# LoRa-Power.net
KiCad netlist of a schematic drawn in EAGLE
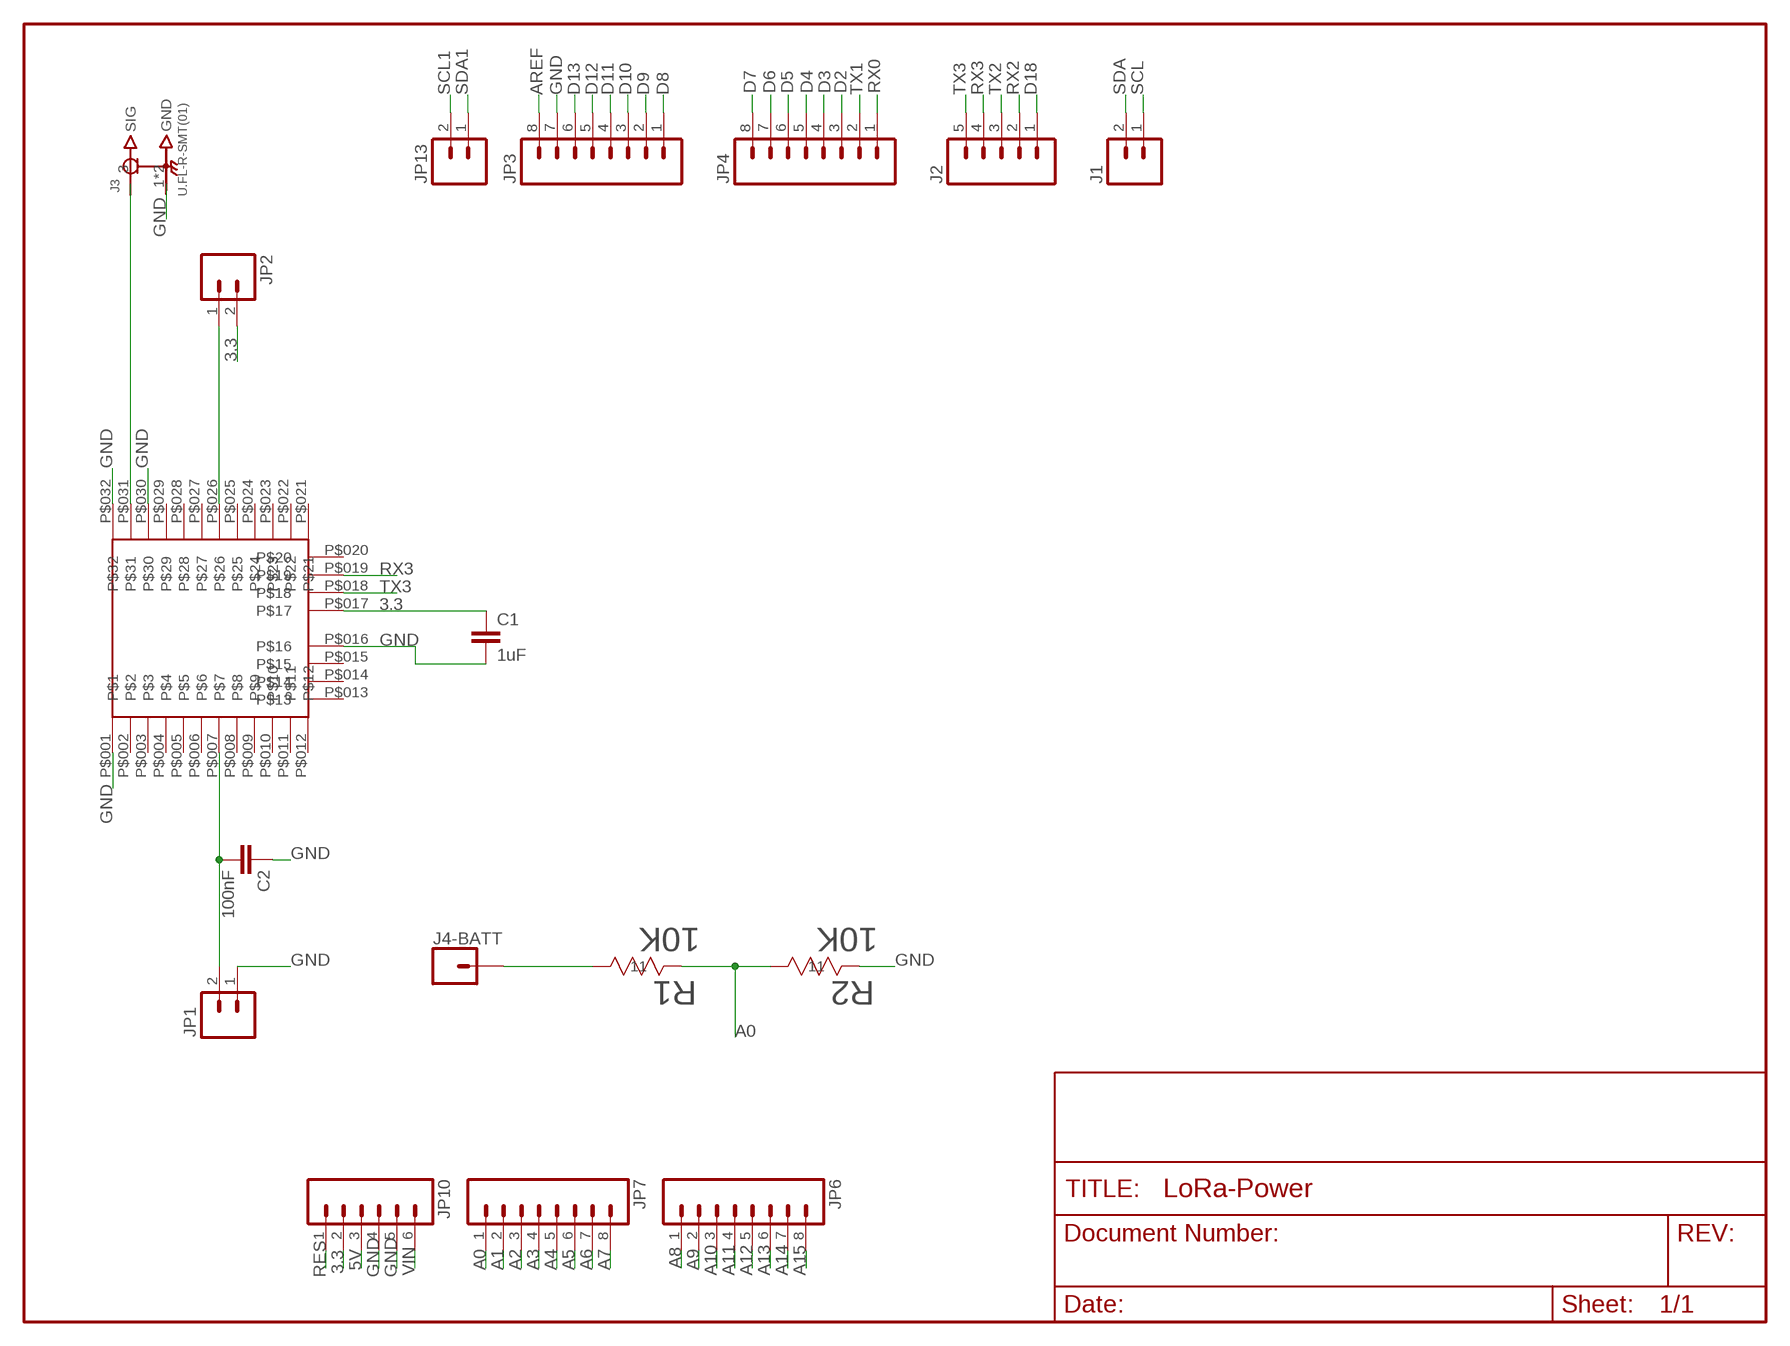
[diagram p0: schematic, sheet 1, part 1 of 2]
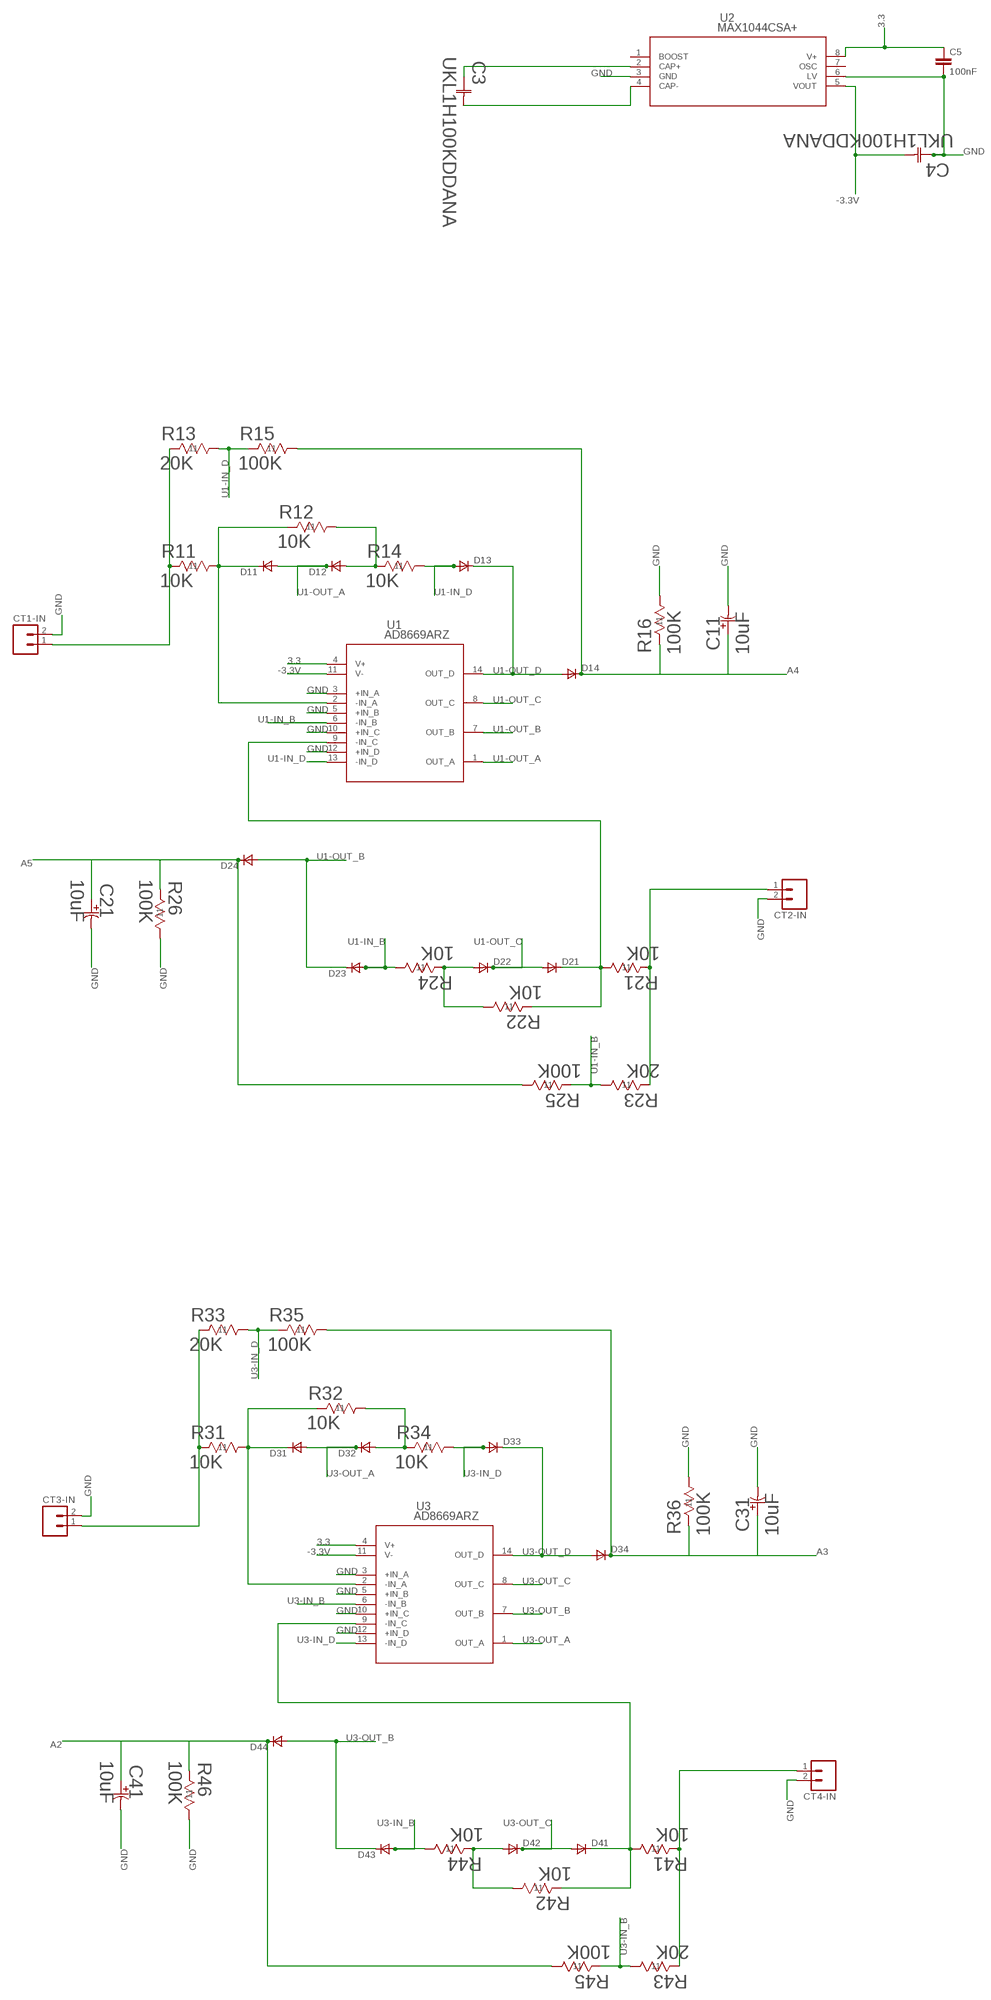
[diagram p1: schematic, sheet 1, part 2 of 2]

(export (version "E")
  (design (tool "Eeschema 10.0.6"))
  (components
    (comp (ref "C1")
      (value "1uF")
      (footprint "eagle-import:C0603K")
      (libsource (lib "eagle-import") (part "resistor_C-EUC0603K"))
    )
    (comp (ref "C2")
      (value "100nF")
      (footprint "eagle-import:C0603K")
      (libsource (lib "eagle-import") (part "resistor_C-EUC0603K"))
    )
    (comp (ref "C3")
      (value "UKL1H100KDDANA")
      (footprint "eagle-import:U1-E")
      (libsource (lib "eagle-import") (part "UKL1H100KDDANA"))
    )
    (comp (ref "C4")
      (value "UKL1H100KDDANA")
      (footprint "eagle-import:U1-E")
      (libsource (lib "eagle-import") (part "UKL1H100KDDANA"))
    )
    (comp (ref "C5")
      (value "100nF")
      (footprint "eagle-import:C1206K")
      (libsource (lib "eagle-import") (part "C-EUC1206K"))
    )
    (comp (ref "C11")
      (value "10uF")
      (footprint "eagle-import:C1206")
      (fields (field (name "MANUFACTURER_PART_NUMBER") "C1206C106J8RACTU"))
      (libsource (lib "eagle-import") (part "C1206C106J8RACTU"))
    )
    (comp (ref "C21")
      (value "10uF")
      (footprint "eagle-import:C1206")
      (fields (field (name "MANUFACTURER_PART_NUMBER") "C1206C106J8RACTU"))
      (libsource (lib "eagle-import") (part "C1206C106J8RACTU"))
    )
    (comp (ref "C31")
      (value "10uF")
      (footprint "eagle-import:C1206")
      (fields (field (name "MANUFACTURER_PART_NUMBER") "C1206C106J8RACTU"))
      (libsource (lib "eagle-import") (part "C1206C106J8RACTU"))
    )
    (comp (ref "C41")
      (value "10uF")
      (footprint "eagle-import:C1206")
      (fields (field (name "MANUFACTURER_PART_NUMBER") "C1206C106J8RACTU"))
      (libsource (lib "eagle-import") (part "C1206C106J8RACTU"))
    )
    (comp (ref "CT1-IN")
      (value "M02LOCK")
      (footprint "eagle-import:1X02_LOCK")
      (libsource (lib "eagle-import") (part "SparkFun-Connectors_M02LOCK"))
    )
    (comp (ref "CT2-IN")
      (value "M02LOCK")
      (footprint "eagle-import:1X02_LOCK")
      (libsource (lib "eagle-import") (part "SparkFun-Connectors_M02LOCK"))
    )
    (comp (ref "CT3-IN")
      (value "M02LOCK")
      (footprint "eagle-import:1X02_LOCK")
      (libsource (lib "eagle-import") (part "SparkFun-Connectors_M02LOCK"))
    )
    (comp (ref "CT4-IN")
      (value "M02LOCK")
      (footprint "eagle-import:1X02_LOCK")
      (libsource (lib "eagle-import") (part "SparkFun-Connectors_M02LOCK"))
    )
    (comp (ref "D11")
      (value "DSOT23")
      (footprint "eagle-import:SOT-23")
      (fields (field (name "MPN") "CDSOT23-T03"))
      (libsource (lib "eagle-import") (part "DSOT23"))
    )
    (comp (ref "D12")
      (value "DSOT23")
      (footprint "eagle-import:SOT-23")
      (fields (field (name "MPN") "CDSOT23-T03"))
      (libsource (lib "eagle-import") (part "DSOT23"))
    )
    (comp (ref "D13")
      (value "DSOT23")
      (footprint "eagle-import:SOT-23")
      (fields (field (name "MPN") "CDSOT23-T03"))
      (libsource (lib "eagle-import") (part "DSOT23"))
    )
    (comp (ref "D14")
      (value "DSOT23")
      (footprint "eagle-import:SOT-23")
      (fields (field (name "MPN") "CDSOT23-T03"))
      (libsource (lib "eagle-import") (part "DSOT23"))
    )
    (comp (ref "D21")
      (value "DSOT23")
      (footprint "eagle-import:SOT-23")
      (fields (field (name "MPN") "CDSOT23-T03"))
      (libsource (lib "eagle-import") (part "DSOT23"))
    )
    (comp (ref "D22")
      (value "DSOT23")
      (footprint "eagle-import:SOT-23")
      (fields (field (name "MPN") "CDSOT23-T03"))
      (libsource (lib "eagle-import") (part "DSOT23"))
    )
    (comp (ref "D23")
      (value "DSOT23")
      (footprint "eagle-import:SOT-23")
      (fields (field (name "MPN") "CDSOT23-T03"))
      (libsource (lib "eagle-import") (part "DSOT23"))
    )
    (comp (ref "D24")
      (value "DSOT23")
      (footprint "eagle-import:SOT-23")
      (fields (field (name "MPN") "CDSOT23-T03"))
      (libsource (lib "eagle-import") (part "DSOT23"))
    )
    (comp (ref "D31")
      (value "DSOT23")
      (footprint "eagle-import:SOT-23")
      (fields (field (name "MPN") "CDSOT23-T03"))
      (libsource (lib "eagle-import") (part "DSOT23"))
    )
    (comp (ref "D32")
      (value "DSOT23")
      (footprint "eagle-import:SOT-23")
      (fields (field (name "MPN") "CDSOT23-T03"))
      (libsource (lib "eagle-import") (part "DSOT23"))
    )
    (comp (ref "D33")
      (value "DSOT23")
      (footprint "eagle-import:SOT-23")
      (fields (field (name "MPN") "CDSOT23-T03"))
      (libsource (lib "eagle-import") (part "DSOT23"))
    )
    (comp (ref "D34")
      (value "DSOT23")
      (footprint "eagle-import:SOT-23")
      (fields (field (name "MPN") "CDSOT23-T03"))
      (libsource (lib "eagle-import") (part "DSOT23"))
    )
    (comp (ref "D41")
      (value "DSOT23")
      (footprint "eagle-import:SOT-23")
      (fields (field (name "MPN") "CDSOT23-T03"))
      (libsource (lib "eagle-import") (part "DSOT23"))
    )
    (comp (ref "D42")
      (value "DSOT23")
      (footprint "eagle-import:SOT-23")
      (fields (field (name "MPN") "CDSOT23-T03"))
      (libsource (lib "eagle-import") (part "DSOT23"))
    )
    (comp (ref "D43")
      (value "DSOT23")
      (footprint "eagle-import:SOT-23")
      (fields (field (name "MPN") "CDSOT23-T03"))
      (libsource (lib "eagle-import") (part "DSOT23"))
    )
    (comp (ref "D44")
      (value "DSOT23")
      (footprint "eagle-import:SOT-23")
      (fields (field (name "MPN") "CDSOT23-T03"))
      (libsource (lib "eagle-import") (part "DSOT23"))
    )
    (comp (ref "IM1")
      (value "IM880B")
      (footprint "eagle-import:IM880B")
      (libsource (lib "eagle-import") (part "IM880B"))
    )
    (comp (ref "J1")
      (value "M02LOCK")
      (footprint "eagle-import:1X02_LOCK")
      (libsource (lib "eagle-import") (part "SparkFun-Connectors_M02LOCK"))
    )
    (comp (ref "J2")
      (value "M05LOCK")
      (footprint "eagle-import:1X05_LOCK")
      (libsource (lib "eagle-import") (part "M05LOCK"))
    )
    (comp (ref "J3")
      (value "U.FL-R-SMT(01)")
      (footprint "eagle-import:HRS_U.FL-R-SMT(01)")
      (fields (field (name "MF") "Hirose"))
      (libsource (lib "eagle-import") (part "U.FL-R-SMT(01)"))
    )
    (comp (ref "J4-BATT")
      (value "CONN_01")
      (footprint "eagle-import:1X01")
      (libsource (lib "eagle-import") (part "CONN_01"))
    )
    (comp (ref "JP1")
      (value "M02LOCK")
      (footprint "eagle-import:1X02_LOCK")
      (libsource (lib "eagle-import") (part "M02LOCK"))
    )
    (comp (ref "JP2")
      (value "M02LOCK")
      (footprint "eagle-import:1X02_LOCK")
      (libsource (lib "eagle-import") (part "M02LOCK"))
    )
    (comp (ref "JP3")
      (value "M08LOCK")
      (footprint "eagle-import:1X08_LOCK")
      (libsource (lib "eagle-import") (part "M08LOCK"))
    )
    (comp (ref "JP4")
      (value "M08LOCK")
      (footprint "eagle-import:1X08_LOCK")
      (libsource (lib "eagle-import") (part "M08LOCK"))
    )
    (comp (ref "JP6")
      (value "M08LOCK")
      (footprint "eagle-import:1X08_LOCK")
      (libsource (lib "eagle-import") (part "M08LOCK"))
    )
    (comp (ref "JP7")
      (value "M08LOCK")
      (footprint "eagle-import:1X08_LOCK")
      (libsource (lib "eagle-import") (part "M08LOCK"))
    )
    (comp (ref "JP10")
      (value "M06LOCK")
      (footprint "eagle-import:1X06_LOCK")
      (libsource (lib "eagle-import") (part "M06LOCK"))
    )
    (comp (ref "JP13")
      (value "M02LOCK")
      (footprint "eagle-import:1X02_LOCK")
      (libsource (lib "eagle-import") (part "SparkFun-Connectors_M02LOCK"))
    )
    (comp (ref "R1")
      (value "10K")
      (footprint "eagle-import:1206")
      (fields (field (name "MANUFACTURER_PART_NUMBER") "ERA8AEB103V"))
      (libsource (lib "eagle-import") (part "ERA-8AEB103V"))
    )
    (comp (ref "R2")
      (value "10K")
      (footprint "eagle-import:1206")
      (fields (field (name "MANUFACTURER_PART_NUMBER") "ERA8AEB103V"))
      (libsource (lib "eagle-import") (part "ERA-8AEB103V"))
    )
    (comp (ref "R11")
      (value "10K")
      (footprint "eagle-import:1206")
      (fields (field (name "MANUFACTURER_PART_NUMBER") "ERA8AEB103V"))
      (libsource (lib "eagle-import") (part "ERA-8AEB103V"))
    )
    (comp (ref "R12")
      (value "10K")
      (footprint "eagle-import:1206")
      (fields (field (name "MANUFACTURER_PART_NUMBER") "ERA8AEB103V"))
      (libsource (lib "eagle-import") (part "ERA-8AEB103V"))
    )
    (comp (ref "R13")
      (value "20K")
      (footprint "eagle-import:1206")
      (fields (field (name "MANUFACTURER_PART_NUMBER") "ERA8AEB103V"))
      (libsource (lib "eagle-import") (part "ERA-8AEB103V"))
    )
    (comp (ref "R14")
      (value "10K")
      (footprint "eagle-import:1206")
      (fields (field (name "MANUFACTURER_PART_NUMBER") "ERA8AEB103V"))
      (libsource (lib "eagle-import") (part "ERA-8AEB103V"))
    )
    (comp (ref "R15")
      (value "100K")
      (footprint "eagle-import:1206")
      (fields (field (name "MANUFACTURER_PART_NUMBER") "ERA8AEB103V"))
      (libsource (lib "eagle-import") (part "ERA-8AEB103V"))
    )
    (comp (ref "R16")
      (value "100K")
      (footprint "eagle-import:1206")
      (fields (field (name "MANUFACTURER_PART_NUMBER") "ERA8AEB103V"))
      (libsource (lib "eagle-import") (part "ERA-8AEB103V"))
    )
    (comp (ref "R21")
      (value "10K")
      (footprint "eagle-import:1206")
      (fields (field (name "MANUFACTURER_PART_NUMBER") "ERA8AEB103V"))
      (libsource (lib "eagle-import") (part "ERA-8AEB103V"))
    )
    (comp (ref "R22")
      (value "10K")
      (footprint "eagle-import:1206")
      (fields (field (name "MANUFACTURER_PART_NUMBER") "ERA8AEB103V"))
      (libsource (lib "eagle-import") (part "ERA-8AEB103V"))
    )
    (comp (ref "R23")
      (value "20K")
      (footprint "eagle-import:1206")
      (fields (field (name "MANUFACTURER_PART_NUMBER") "ERA8AEB103V"))
      (libsource (lib "eagle-import") (part "ERA-8AEB103V"))
    )
    (comp (ref "R24")
      (value "10K")
      (footprint "eagle-import:1206")
      (fields (field (name "MANUFACTURER_PART_NUMBER") "ERA8AEB103V"))
      (libsource (lib "eagle-import") (part "ERA-8AEB103V"))
    )
    (comp (ref "R25")
      (value "100K")
      (footprint "eagle-import:1206")
      (fields (field (name "MANUFACTURER_PART_NUMBER") "ERA8AEB103V"))
      (libsource (lib "eagle-import") (part "ERA-8AEB103V"))
    )
    (comp (ref "R26")
      (value "100K")
      (footprint "eagle-import:1206")
      (fields (field (name "MANUFACTURER_PART_NUMBER") "ERA8AEB103V"))
      (libsource (lib "eagle-import") (part "ERA-8AEB103V"))
    )
    (comp (ref "R31")
      (value "10K")
      (footprint "eagle-import:1206")
      (fields (field (name "MANUFACTURER_PART_NUMBER") "ERA8AEB103V"))
      (libsource (lib "eagle-import") (part "ERA-8AEB103V"))
    )
    (comp (ref "R32")
      (value "10K")
      (footprint "eagle-import:1206")
      (fields (field (name "MANUFACTURER_PART_NUMBER") "ERA8AEB103V"))
      (libsource (lib "eagle-import") (part "ERA-8AEB103V"))
    )
    (comp (ref "R33")
      (value "20K")
      (footprint "eagle-import:1206")
      (fields (field (name "MANUFACTURER_PART_NUMBER") "ERA8AEB103V"))
      (libsource (lib "eagle-import") (part "ERA-8AEB103V"))
    )
    (comp (ref "R34")
      (value "10K")
      (footprint "eagle-import:1206")
      (fields (field (name "MANUFACTURER_PART_NUMBER") "ERA8AEB103V"))
      (libsource (lib "eagle-import") (part "ERA-8AEB103V"))
    )
    (comp (ref "R35")
      (value "100K")
      (footprint "eagle-import:1206")
      (fields (field (name "MANUFACTURER_PART_NUMBER") "ERA8AEB103V"))
      (libsource (lib "eagle-import") (part "ERA-8AEB103V"))
    )
    (comp (ref "R36")
      (value "100K")
      (footprint "eagle-import:1206")
      (fields (field (name "MANUFACTURER_PART_NUMBER") "ERA8AEB103V"))
      (libsource (lib "eagle-import") (part "ERA-8AEB103V"))
    )
    (comp (ref "R41")
      (value "10K")
      (footprint "eagle-import:1206")
      (fields (field (name "MANUFACTURER_PART_NUMBER") "ERA8AEB103V"))
      (libsource (lib "eagle-import") (part "ERA-8AEB103V"))
    )
    (comp (ref "R42")
      (value "10K")
      (footprint "eagle-import:1206")
      (fields (field (name "MANUFACTURER_PART_NUMBER") "ERA8AEB103V"))
      (libsource (lib "eagle-import") (part "ERA-8AEB103V"))
    )
    (comp (ref "R43")
      (value "20K")
      (footprint "eagle-import:1206")
      (fields (field (name "MANUFACTURER_PART_NUMBER") "ERA8AEB103V"))
      (libsource (lib "eagle-import") (part "ERA-8AEB103V"))
    )
    (comp (ref "R44")
      (value "10K")
      (footprint "eagle-import:1206")
      (fields (field (name "MANUFACTURER_PART_NUMBER") "ERA8AEB103V"))
      (libsource (lib "eagle-import") (part "ERA-8AEB103V"))
    )
    (comp (ref "R45")
      (value "100K")
      (footprint "eagle-import:1206")
      (fields (field (name "MANUFACTURER_PART_NUMBER") "ERA8AEB103V"))
      (libsource (lib "eagle-import") (part "ERA-8AEB103V"))
    )
    (comp (ref "R46")
      (value "100K")
      (footprint "eagle-import:1206")
      (fields (field (name "MANUFACTURER_PART_NUMBER") "ERA8AEB103V"))
      (libsource (lib "eagle-import") (part "ERA-8AEB103V"))
    )
    (comp (ref "U1")
      (value "AD8669ARZ")
      (footprint "eagle-import:R_14")
      (libsource (lib "eagle-import") (part "AD8669ARZ"))
    )
    (comp (ref "U2")
      (value "MAX1044CSA+")
      (footprint "eagle-import:21-0041B_8")
      (libsource (lib "eagle-import") (part "MAX1044CSA+"))
    )
    (comp (ref "U3")
      (value "AD8669ARZ")
      (footprint "eagle-import:R_14")
      (libsource (lib "eagle-import") (part "AD8669ARZ"))
    )
  )
  (nets
    (net (code "1") (name "/-3.3V") (class "Default")
      (node (ref "C4") (pin "2") (pinfunction "22_2") (pintype "passive"))
      (node (ref "U1") (pin "11") (pinfunction "V-_11") (pintype "passive"))
      (node (ref "U2") (pin "5") (pinfunction "VOUT_5") (pintype "output"))
      (node (ref "U3") (pin "11") (pinfunction "V-_11") (pintype "passive"))
    )
    (net (code "2") (name "/3.3") (class "Default")
      (node (ref "C1") (pin "1") (pinfunction "1_1") (pintype "passive"))
      (node (ref "C5") (pin "1") (pinfunction "1_1") (pintype "passive"))
      (node (ref "IM1") (pin "P$017") (pinfunction "P$17_P$017") (pintype "bidirectional"))
      (node (ref "JP10") (pin "2") (pinfunction "2_2") (pintype "passive"))
      (node (ref "JP2") (pin "2") (pinfunction "2_2") (pintype "passive"))
      (node (ref "U1") (pin "4") (pinfunction "V+_4") (pintype "passive"))
      (node (ref "U2") (pin "8") (pinfunction "V+_8") (pintype "power_in"))
      (node (ref "U3") (pin "4") (pinfunction "V+_4") (pintype "passive"))
    )
    (net (code "3") (name "/5V") (class "Default")
      (node (ref "JP10") (pin "3") (pinfunction "3_3") (pintype "passive"))
    )
    (net (code "4") (name "/A0") (class "Default")
      (node (ref "JP7") (pin "1") (pinfunction "1_1") (pintype "passive"))
      (node (ref "R1") (pin "1") (pinfunction "11_1") (pintype "passive"))
      (node (ref "R2") (pin "2") (pinfunction "22_2") (pintype "passive"))
    )
    (net (code "5") (name "/A1") (class "Default")
      (node (ref "JP7") (pin "2") (pinfunction "2_2") (pintype "passive"))
    )
    (net (code "6") (name "/A2") (class "Default")
      (node (ref "C41") (pin "1") (pinfunction "11_1") (pintype "passive"))
      (node (ref "D44") (pin "1") (pinfunction "C_1") (pintype "passive"))
      (node (ref "JP7") (pin "3") (pinfunction "3_3") (pintype "passive"))
      (node (ref "R45") (pin "2") (pinfunction "22_2") (pintype "passive"))
      (node (ref "R46") (pin "1") (pinfunction "11_1") (pintype "passive"))
    )
    (net (code "7") (name "/A3") (class "Default")
      (node (ref "C31") (pin "1") (pinfunction "11_1") (pintype "passive"))
      (node (ref "D34") (pin "1") (pinfunction "C_1") (pintype "passive"))
      (node (ref "JP7") (pin "4") (pinfunction "4_4") (pintype "passive"))
      (node (ref "R35") (pin "2") (pinfunction "22_2") (pintype "passive"))
      (node (ref "R36") (pin "1") (pinfunction "11_1") (pintype "passive"))
    )
    (net (code "8") (name "/A4") (class "Default")
      (node (ref "C11") (pin "1") (pinfunction "11_1") (pintype "passive"))
      (node (ref "D14") (pin "1") (pinfunction "C_1") (pintype "passive"))
      (node (ref "JP7") (pin "5") (pinfunction "5_5") (pintype "passive"))
      (node (ref "R15") (pin "2") (pinfunction "22_2") (pintype "passive"))
      (node (ref "R16") (pin "1") (pinfunction "11_1") (pintype "passive"))
    )
    (net (code "9") (name "/A5") (class "Default")
      (node (ref "C21") (pin "1") (pinfunction "11_1") (pintype "passive"))
      (node (ref "D24") (pin "1") (pinfunction "C_1") (pintype "passive"))
      (node (ref "JP7") (pin "6") (pinfunction "6_6") (pintype "passive"))
      (node (ref "R25") (pin "2") (pinfunction "22_2") (pintype "passive"))
      (node (ref "R26") (pin "1") (pinfunction "11_1") (pintype "passive"))
    )
    (net (code "10") (name "/A6") (class "Default")
      (node (ref "JP7") (pin "7") (pinfunction "7_7") (pintype "passive"))
    )
    (net (code "11") (name "/A7") (class "Default")
      (node (ref "JP7") (pin "8") (pinfunction "8_8") (pintype "passive"))
    )
    (net (code "12") (name "/A8") (class "Default")
      (node (ref "JP6") (pin "1") (pinfunction "1_1") (pintype "passive"))
    )
    (net (code "13") (name "/A9") (class "Default")
      (node (ref "JP6") (pin "2") (pinfunction "2_2") (pintype "passive"))
    )
    (net (code "14") (name "/A10") (class "Default")
      (node (ref "JP6") (pin "3") (pinfunction "3_3") (pintype "passive"))
    )
    (net (code "15") (name "/A11") (class "Default")
      (node (ref "JP6") (pin "4") (pinfunction "4_4") (pintype "passive"))
    )
    (net (code "16") (name "/A12") (class "Default")
      (node (ref "JP6") (pin "5") (pinfunction "5_5") (pintype "passive"))
    )
    (net (code "17") (name "/A13") (class "Default")
      (node (ref "JP6") (pin "6") (pinfunction "6_6") (pintype "passive"))
    )
    (net (code "18") (name "/A14") (class "Default")
      (node (ref "JP6") (pin "7") (pinfunction "7_7") (pintype "passive"))
    )
    (net (code "19") (name "/A15") (class "Default")
      (node (ref "JP6") (pin "8") (pinfunction "8_8") (pintype "passive"))
    )
    (net (code "20") (name "/AREF") (class "Default")
      (node (ref "JP3") (pin "8") (pinfunction "8_8") (pintype "passive"))
    )
    (net (code "21") (name "/D2") (class "Default")
      (node (ref "JP4") (pin "3") (pinfunction "3_3") (pintype "passive"))
    )
    (net (code "22") (name "/D3") (class "Default")
      (node (ref "JP4") (pin "4") (pinfunction "4_4") (pintype "passive"))
    )
    (net (code "23") (name "/D4") (class "Default")
      (node (ref "JP4") (pin "5") (pinfunction "5_5") (pintype "passive"))
    )
    (net (code "24") (name "/D5") (class "Default")
      (node (ref "JP4") (pin "6") (pinfunction "6_6") (pintype "passive"))
    )
    (net (code "25") (name "/D6") (class "Default")
      (node (ref "JP4") (pin "7") (pinfunction "7_7") (pintype "passive"))
    )
    (net (code "26") (name "/D7") (class "Default")
      (node (ref "JP4") (pin "8") (pinfunction "8_8") (pintype "passive"))
    )
    (net (code "27") (name "/D8") (class "Default")
      (node (ref "JP3") (pin "1") (pinfunction "1_1") (pintype "passive"))
    )
    (net (code "28") (name "/D9") (class "Default")
      (node (ref "JP3") (pin "2") (pinfunction "2_2") (pintype "passive"))
    )
    (net (code "29") (name "/D10") (class "Default")
      (node (ref "JP3") (pin "3") (pinfunction "3_3") (pintype "passive"))
    )
    (net (code "30") (name "/D11") (class "Default")
      (node (ref "JP3") (pin "4") (pinfunction "4_4") (pintype "passive"))
    )
    (net (code "31") (name "/D12") (class "Default")
      (node (ref "JP3") (pin "5") (pinfunction "5_5") (pintype "passive"))
    )
    (net (code "32") (name "/D13") (class "Default")
      (node (ref "JP3") (pin "6") (pinfunction "6_6") (pintype "passive"))
    )
    (net (code "33") (name "/D18") (class "Default")
      (node (ref "J2") (pin "1") (pinfunction "1_1") (pintype "passive"))
    )
    (net (code "34") (name "/GND") (class "Default")
      (node (ref "C1") (pin "2") (pinfunction "2_2") (pintype "passive"))
      (node (ref "C11") (pin "2") (pinfunction "22_2") (pintype "passive"))
      (node (ref "C2") (pin "1") (pinfunction "1_1") (pintype "passive"))
      (node (ref "C21") (pin "2") (pinfunction "22_2") (pintype "passive"))
      (node (ref "C31") (pin "2") (pinfunction "22_2") (pintype "passive"))
      (node (ref "C4") (pin "1") (pinfunction "11_1") (pintype "passive"))
      (node (ref "C41") (pin "2") (pinfunction "22_2") (pintype "passive"))
      (node (ref "C5") (pin "2") (pinfunction "2_2") (pintype "passive"))
      (node (ref "CT1-IN") (pin "2") (pinfunction "2_2") (pintype "passive"))
      (node (ref "CT2-IN") (pin "2") (pinfunction "2_2") (pintype "passive"))
      (node (ref "CT3-IN") (pin "2") (pinfunction "2_2") (pintype "passive"))
      (node (ref "CT4-IN") (pin "2") (pinfunction "2_2") (pintype "passive"))
      (node (ref "IM1") (pin "P$001") (pinfunction "P$1_P$001") (pintype "bidirectional"))
      (node (ref "IM1") (pin "P$016") (pinfunction "P$16_P$016") (pintype "bidirectional"))
      (node (ref "IM1") (pin "P$030") (pinfunction "P$30_P$030") (pintype "bidirectional"))
      (node (ref "IM1") (pin "P$032") (pinfunction "P$32_P$032") (pintype "bidirectional"))
      (node (ref "J3") (pin "1") (pinfunction "GND_1") (pintype "passive"))
      (node (ref "J3") (pin "2") (pinfunction "GND_2") (pintype "passive"))
      (node (ref "JP1") (pin "1") (pinfunction "1_1") (pintype "passive"))
      (node (ref "JP10") (pin "4") (pinfunction "4_4") (pintype "passive"))
      (node (ref "JP10") (pin "5") (pinfunction "5_5") (pintype "passive"))
      (node (ref "JP3") (pin "7") (pinfunction "7_7") (pintype "passive"))
      (node (ref "R16") (pin "2") (pinfunction "22_2") (pintype "passive"))
      (node (ref "R2") (pin "1") (pinfunction "11_1") (pintype "passive"))
      (node (ref "R26") (pin "2") (pinfunction "22_2") (pintype "passive"))
      (node (ref "R36") (pin "2") (pinfunction "22_2") (pintype "passive"))
      (node (ref "R46") (pin "2") (pinfunction "22_2") (pintype "passive"))
      (node (ref "U1") (pin "10") (pinfunction "+IN_C_10") (pintype "passive"))
      (node (ref "U1") (pin "12") (pinfunction "+IN_D_12") (pintype "passive"))
      (node (ref "U1") (pin "3") (pinfunction "+IN_A_3") (pintype "passive"))
      (node (ref "U1") (pin "5") (pinfunction "+IN_B_5") (pintype "passive"))
      (node (ref "U2") (pin "3") (pinfunction "GND_3") (pintype "power_in"))
      (node (ref "U2") (pin "6") (pinfunction "LV_6") (pintype "input"))
      (node (ref "U3") (pin "10") (pinfunction "+IN_C_10") (pintype "passive"))
      (node (ref "U3") (pin "12") (pinfunction "+IN_D_12") (pintype "passive"))
      (node (ref "U3") (pin "3") (pinfunction "+IN_A_3") (pintype "passive"))
      (node (ref "U3") (pin "5") (pinfunction "+IN_B_5") (pintype "passive"))
    )
    (net (code "35") (name "/RES") (class "Default")
      (node (ref "JP10") (pin "1") (pinfunction "1_1") (pintype "passive"))
    )
    (net (code "36") (name "/RX0") (class "Default")
      (node (ref "JP4") (pin "1") (pinfunction "1_1") (pintype "passive"))
    )
    (net (code "37") (name "/RX2") (class "Default")
      (node (ref "J2") (pin "2") (pinfunction "2_2") (pintype "passive"))
    )
    (net (code "38") (name "/RX3") (class "Default")
      (node (ref "IM1") (pin "P$019") (pinfunction "P$19_P$019") (pintype "bidirectional"))
      (node (ref "J2") (pin "4") (pinfunction "4_4") (pintype "passive"))
    )
    (net (code "39") (name "/SCL") (class "Default")
      (node (ref "J1") (pin "1") (pinfunction "1_1") (pintype "passive"))
    )
    (net (code "40") (name "/SCL1") (class "Default")
      (node (ref "JP13") (pin "2") (pinfunction "2_2") (pintype "passive"))
    )
    (net (code "41") (name "/SDA") (class "Default")
      (node (ref "J1") (pin "2") (pinfunction "2_2") (pintype "passive"))
    )
    (net (code "42") (name "/SDA1") (class "Default")
      (node (ref "JP13") (pin "1") (pinfunction "1_1") (pintype "passive"))
    )
    (net (code "43") (name "/TX1") (class "Default")
      (node (ref "JP4") (pin "2") (pinfunction "2_2") (pintype "passive"))
    )
    (net (code "44") (name "/TX2") (class "Default")
      (node (ref "J2") (pin "3") (pinfunction "3_3") (pintype "passive"))
    )
    (net (code "45") (name "/TX3") (class "Default")
      (node (ref "IM1") (pin "P$018") (pinfunction "P$18_P$018") (pintype "bidirectional"))
      (node (ref "J2") (pin "5") (pinfunction "5_5") (pintype "passive"))
    )
    (net (code "46") (name "/U1-IN_B") (class "Default")
      (node (ref "D23") (pin "3") (pinfunction "A_3") (pintype "passive"))
      (node (ref "R23") (pin "2") (pinfunction "22_2") (pintype "passive"))
      (node (ref "R24") (pin "2") (pinfunction "22_2") (pintype "passive"))
      (node (ref "R25") (pin "1") (pinfunction "11_1") (pintype "passive"))
      (node (ref "U1") (pin "6") (pinfunction "-IN_B_6") (pintype "passive"))
    )
    (net (code "47") (name "/U1-IN_D") (class "Default")
      (node (ref "D13") (pin "3") (pinfunction "A_3") (pintype "passive"))
      (node (ref "R13") (pin "2") (pinfunction "22_2") (pintype "passive"))
      (node (ref "R14") (pin "2") (pinfunction "22_2") (pintype "passive"))
      (node (ref "R15") (pin "1") (pinfunction "11_1") (pintype "passive"))
      (node (ref "U1") (pin "13") (pinfunction "-IN_D_13") (pintype "passive"))
    )
    (net (code "48") (name "/U1-OUT_A") (class "Default")
      (node (ref "D11") (pin "3") (pinfunction "A_3") (pintype "passive"))
      (node (ref "D12") (pin "1") (pinfunction "C_1") (pintype "passive"))
      (node (ref "U1") (pin "1") (pinfunction "OUT_A_1") (pintype "passive"))
    )
    (net (code "49") (name "/U1-OUT_B") (class "Default")
      (node (ref "D23") (pin "1") (pinfunction "C_1") (pintype "passive"))
      (node (ref "D24") (pin "3") (pinfunction "A_3") (pintype "passive"))
      (node (ref "U1") (pin "7") (pinfunction "OUT_B_7") (pintype "passive"))
    )
    (net (code "50") (name "/U1-OUT_C") (class "Default")
      (node (ref "D21") (pin "3") (pinfunction "A_3") (pintype "passive"))
      (node (ref "D22") (pin "1") (pinfunction "C_1") (pintype "passive"))
      (node (ref "U1") (pin "8") (pinfunction "OUT_C_8") (pintype "passive"))
    )
    (net (code "51") (name "/U1-OUT_D") (class "Default")
      (node (ref "D13") (pin "1") (pinfunction "C_1") (pintype "passive"))
      (node (ref "D14") (pin "3") (pinfunction "A_3") (pintype "passive"))
      (node (ref "U1") (pin "14") (pinfunction "OUT_D_14") (pintype "passive"))
    )
    (net (code "52") (name "/U3-IN_B") (class "Default")
      (node (ref "D43") (pin "3") (pinfunction "A_3") (pintype "passive"))
      (node (ref "R43") (pin "2") (pinfunction "22_2") (pintype "passive"))
      (node (ref "R44") (pin "2") (pinfunction "22_2") (pintype "passive"))
      (node (ref "R45") (pin "1") (pinfunction "11_1") (pintype "passive"))
      (node (ref "U3") (pin "6") (pinfunction "-IN_B_6") (pintype "passive"))
    )
    (net (code "53") (name "/U3-IN_D") (class "Default")
      (node (ref "D33") (pin "3") (pinfunction "A_3") (pintype "passive"))
      (node (ref "R33") (pin "2") (pinfunction "22_2") (pintype "passive"))
      (node (ref "R34") (pin "2") (pinfunction "22_2") (pintype "passive"))
      (node (ref "R35") (pin "1") (pinfunction "11_1") (pintype "passive"))
      (node (ref "U3") (pin "13") (pinfunction "-IN_D_13") (pintype "passive"))
    )
    (net (code "54") (name "/U3-OUT_A") (class "Default")
      (node (ref "D31") (pin "3") (pinfunction "A_3") (pintype "passive"))
      (node (ref "D32") (pin "1") (pinfunction "C_1") (pintype "passive"))
      (node (ref "U3") (pin "1") (pinfunction "OUT_A_1") (pintype "passive"))
    )
    (net (code "55") (name "/U3-OUT_B") (class "Default")
      (node (ref "D43") (pin "1") (pinfunction "C_1") (pintype "passive"))
      (node (ref "D44") (pin "3") (pinfunction "A_3") (pintype "passive"))
      (node (ref "U3") (pin "7") (pinfunction "OUT_B_7") (pintype "passive"))
    )
    (net (code "56") (name "/U3-OUT_C") (class "Default")
      (node (ref "D41") (pin "3") (pinfunction "A_3") (pintype "passive"))
      (node (ref "D42") (pin "1") (pinfunction "C_1") (pintype "passive"))
      (node (ref "U3") (pin "8") (pinfunction "OUT_C_8") (pintype "passive"))
    )
    (net (code "57") (name "/U3-OUT_D") (class "Default")
      (node (ref "D33") (pin "1") (pinfunction "C_1") (pintype "passive"))
      (node (ref "D34") (pin "3") (pinfunction "A_3") (pintype "passive"))
      (node (ref "U3") (pin "14") (pinfunction "OUT_D_14") (pintype "passive"))
    )
    (net (code "58") (name "/VIN") (class "Default")
      (node (ref "JP10") (pin "6") (pinfunction "6_6") (pintype "passive"))
    )
    (net (code "59") (name "Net-(C3-11)") (class "Default")
      (node (ref "C3") (pin "1") (pinfunction "11_1") (pintype "passive"))
      (node (ref "U2") (pin "2") (pinfunction "CAP+_2") (pintype "passive"))
    )
    (net (code "60") (name "Net-(C3-22)") (class "Default")
      (node (ref "C3") (pin "2") (pinfunction "22_2") (pintype "passive"))
      (node (ref "U2") (pin "4") (pinfunction "CAP-_4") (pintype "passive"))
    )
    (net (code "61") (name "Net-(D11-C)") (class "Default")
      (node (ref "D11") (pin "1") (pinfunction "C_1") (pintype "passive"))
      (node (ref "R11") (pin "2") (pinfunction "22_2") (pintype "passive"))
      (node (ref "R12") (pin "1") (pinfunction "11_1") (pintype "passive"))
      (node (ref "U1") (pin "2") (pinfunction "-IN_A_2") (pintype "passive"))
    )
    (net (code "62") (name "Net-(D12-A)") (class "Default")
      (node (ref "D12") (pin "3") (pinfunction "A_3") (pintype "passive"))
      (node (ref "R12") (pin "2") (pinfunction "22_2") (pintype "passive"))
      (node (ref "R14") (pin "1") (pinfunction "11_1") (pintype "passive"))
    )
    (net (code "63") (name "Net-(D21-C)") (class "Default")
      (node (ref "D21") (pin "1") (pinfunction "C_1") (pintype "passive"))
      (node (ref "R21") (pin "2") (pinfunction "22_2") (pintype "passive"))
      (node (ref "R22") (pin "1") (pinfunction "11_1") (pintype "passive"))
      (node (ref "U1") (pin "9") (pinfunction "-IN_C_9") (pintype "passive"))
    )
    (net (code "64") (name "Net-(D22-A)") (class "Default")
      (node (ref "D22") (pin "3") (pinfunction "A_3") (pintype "passive"))
      (node (ref "R22") (pin "2") (pinfunction "22_2") (pintype "passive"))
      (node (ref "R24") (pin "1") (pinfunction "11_1") (pintype "passive"))
    )
    (net (code "65") (name "Net-(D31-C)") (class "Default")
      (node (ref "D31") (pin "1") (pinfunction "C_1") (pintype "passive"))
      (node (ref "R31") (pin "2") (pinfunction "22_2") (pintype "passive"))
      (node (ref "R32") (pin "1") (pinfunction "11_1") (pintype "passive"))
      (node (ref "U3") (pin "2") (pinfunction "-IN_A_2") (pintype "passive"))
    )
    (net (code "66") (name "Net-(D32-A)") (class "Default")
      (node (ref "D32") (pin "3") (pinfunction "A_3") (pintype "passive"))
      (node (ref "R32") (pin "2") (pinfunction "22_2") (pintype "passive"))
      (node (ref "R34") (pin "1") (pinfunction "11_1") (pintype "passive"))
    )
    (net (code "67") (name "Net-(D41-C)") (class "Default")
      (node (ref "D41") (pin "1") (pinfunction "C_1") (pintype "passive"))
      (node (ref "R41") (pin "2") (pinfunction "22_2") (pintype "passive"))
      (node (ref "R42") (pin "1") (pinfunction "11_1") (pintype "passive"))
      (node (ref "U3") (pin "9") (pinfunction "-IN_C_9") (pintype "passive"))
    )
    (net (code "68") (name "Net-(D42-A)") (class "Default")
      (node (ref "D42") (pin "3") (pinfunction "A_3") (pintype "passive"))
      (node (ref "R42") (pin "2") (pinfunction "22_2") (pintype "passive"))
      (node (ref "R44") (pin "1") (pinfunction "11_1") (pintype "passive"))
    )
    (net (code "69") (name "Net-(IM1-P$7)") (class "Default")
      (node (ref "C2") (pin "2") (pinfunction "2_2") (pintype "passive"))
      (node (ref "IM1") (pin "P$007") (pinfunction "P$7_P$007") (pintype "bidirectional"))
      (node (ref "JP1") (pin "2") (pinfunction "2_2") (pintype "passive"))
    )
    (net (code "70") (name "Net-(IM1-P$26)") (class "Default")
      (node (ref "IM1") (pin "P$026") (pinfunction "P$26_P$026") (pintype "bidirectional"))
      (node (ref "JP2") (pin "1") (pinfunction "1_1") (pintype "passive"))
    )
    (net (code "71") (name "Net-(IM1-P$31)") (class "Default")
      (node (ref "IM1") (pin "P$031") (pinfunction "P$31_P$031") (pintype "bidirectional"))
      (node (ref "J3") (pin "3") (pinfunction "SIG_3") (pintype "passive"))
    )
    (net (code "72") (name "Net-(R1-22)") (class "Default")
      (node (ref "J4-BATT") (pin "1") (pinfunction "1_1") (pintype "passive"))
      (node (ref "R1") (pin "2") (pinfunction "22_2") (pintype "passive"))
    )
    (net (code "73") (name "Net-(R11-11)") (class "Default")
      (node (ref "CT1-IN") (pin "1") (pinfunction "1_1") (pintype "passive"))
      (node (ref "R11") (pin "1") (pinfunction "11_1") (pintype "passive"))
      (node (ref "R13") (pin "1") (pinfunction "11_1") (pintype "passive"))
    )
    (net (code "74") (name "Net-(R21-11)") (class "Default")
      (node (ref "CT2-IN") (pin "1") (pinfunction "1_1") (pintype "passive"))
      (node (ref "R21") (pin "1") (pinfunction "11_1") (pintype "passive"))
      (node (ref "R23") (pin "1") (pinfunction "11_1") (pintype "passive"))
    )
    (net (code "75") (name "Net-(R31-11)") (class "Default")
      (node (ref "CT3-IN") (pin "1") (pinfunction "1_1") (pintype "passive"))
      (node (ref "R31") (pin "1") (pinfunction "11_1") (pintype "passive"))
      (node (ref "R33") (pin "1") (pinfunction "11_1") (pintype "passive"))
    )
    (net (code "76") (name "Net-(R41-11)") (class "Default")
      (node (ref "CT4-IN") (pin "1") (pinfunction "1_1") (pintype "passive"))
      (node (ref "R41") (pin "1") (pinfunction "11_1") (pintype "passive"))
      (node (ref "R43") (pin "1") (pinfunction "11_1") (pintype "passive"))
    )
    (net (code "77") (name "unconnected-(IM1-P$2-PadP$002)") (class "Default")
      (node (ref "IM1") (pin "P$002") (pinfunction "P$2_P$002") (pintype "bidirectional"))
    )
    (net (code "78") (name "unconnected-(IM1-P$3-PadP$003)") (class "Default")
      (node (ref "IM1") (pin "P$003") (pinfunction "P$3_P$003") (pintype "bidirectional"))
    )
    (net (code "79") (name "unconnected-(IM1-P$4-PadP$004)") (class "Default")
      (node (ref "IM1") (pin "P$004") (pinfunction "P$4_P$004") (pintype "bidirectional"))
    )
    (net (code "80") (name "unconnected-(IM1-P$5-PadP$005)") (class "Default")
      (node (ref "IM1") (pin "P$005") (pinfunction "P$5_P$005") (pintype "bidirectional"))
    )
    (net (code "81") (name "unconnected-(IM1-P$6-PadP$006)") (class "Default")
      (node (ref "IM1") (pin "P$006") (pinfunction "P$6_P$006") (pintype "bidirectional"))
    )
    (net (code "82") (name "unconnected-(IM1-P$8-PadP$008)") (class "Default")
      (node (ref "IM1") (pin "P$008") (pinfunction "P$8_P$008") (pintype "bidirectional"))
    )
    (net (code "83") (name "unconnected-(IM1-P$9-PadP$009)") (class "Default")
      (node (ref "IM1") (pin "P$009") (pinfunction "P$9_P$009") (pintype "bidirectional"))
    )
    (net (code "84") (name "unconnected-(IM1-P$10-PadP$010)") (class "Default")
      (node (ref "IM1") (pin "P$010") (pinfunction "P$10_P$010") (pintype "bidirectional"))
    )
    (net (code "85") (name "unconnected-(IM1-P$11-PadP$011)") (class "Default")
      (node (ref "IM1") (pin "P$011") (pinfunction "P$11_P$011") (pintype "bidirectional"))
    )
    (net (code "86") (name "unconnected-(IM1-P$12-PadP$012)") (class "Default")
      (node (ref "IM1") (pin "P$012") (pinfunction "P$12_P$012") (pintype "bidirectional"))
    )
    (net (code "87") (name "unconnected-(IM1-P$13-PadP$013)") (class "Default")
      (node (ref "IM1") (pin "P$013") (pinfunction "P$13_P$013") (pintype "bidirectional"))
    )
    (net (code "88") (name "unconnected-(IM1-P$14-PadP$014)") (class "Default")
      (node (ref "IM1") (pin "P$014") (pinfunction "P$14_P$014") (pintype "bidirectional"))
    )
    (net (code "89") (name "unconnected-(IM1-P$15-PadP$015)") (class "Default")
      (node (ref "IM1") (pin "P$015") (pinfunction "P$15_P$015") (pintype "bidirectional"))
    )
    (net (code "90") (name "unconnected-(IM1-P$20-PadP$020)") (class "Default")
      (node (ref "IM1") (pin "P$020") (pinfunction "P$20_P$020") (pintype "bidirectional"))
    )
    (net (code "91") (name "unconnected-(IM1-P$21-PadP$021)") (class "Default")
      (node (ref "IM1") (pin "P$021") (pinfunction "P$21_P$021") (pintype "bidirectional"))
    )
    (net (code "92") (name "unconnected-(IM1-P$22-PadP$022)") (class "Default")
      (node (ref "IM1") (pin "P$022") (pinfunction "P$22_P$022") (pintype "bidirectional"))
    )
    (net (code "93") (name "unconnected-(IM1-P$23-PadP$023)") (class "Default")
      (node (ref "IM1") (pin "P$023") (pinfunction "P$23_P$023") (pintype "bidirectional"))
    )
    (net (code "94") (name "unconnected-(IM1-P$24-PadP$024)") (class "Default")
      (node (ref "IM1") (pin "P$024") (pinfunction "P$24_P$024") (pintype "bidirectional"))
    )
    (net (code "95") (name "unconnected-(IM1-P$25-PadP$025)") (class "Default")
      (node (ref "IM1") (pin "P$025") (pinfunction "P$25_P$025") (pintype "bidirectional"))
    )
    (net (code "96") (name "unconnected-(IM1-P$27-PadP$027)") (class "Default")
      (node (ref "IM1") (pin "P$027") (pinfunction "P$27_P$027") (pintype "bidirectional"))
    )
    (net (code "97") (name "unconnected-(IM1-P$28-PadP$028)") (class "Default")
      (node (ref "IM1") (pin "P$028") (pinfunction "P$28_P$028") (pintype "bidirectional"))
    )
    (net (code "98") (name "unconnected-(IM1-P$29-PadP$029)") (class "Default")
      (node (ref "IM1") (pin "P$029") (pinfunction "P$29_P$029") (pintype "bidirectional"))
    )
    (net (code "99") (name "unconnected-(U2-BOOST-Pad1)") (class "Default")
      (node (ref "U2") (pin "1") (pinfunction "BOOST_1") (pintype "passive"))
    )
    (net (code "100") (name "unconnected-(U2-OSC-Pad7)") (class "Default")
      (node (ref "U2") (pin "7") (pinfunction "OSC_7") (pintype "input"))
    )
  )
)
